# RaspberryPi.net
KiCad netlist of a schematic drawn in Altium Designer
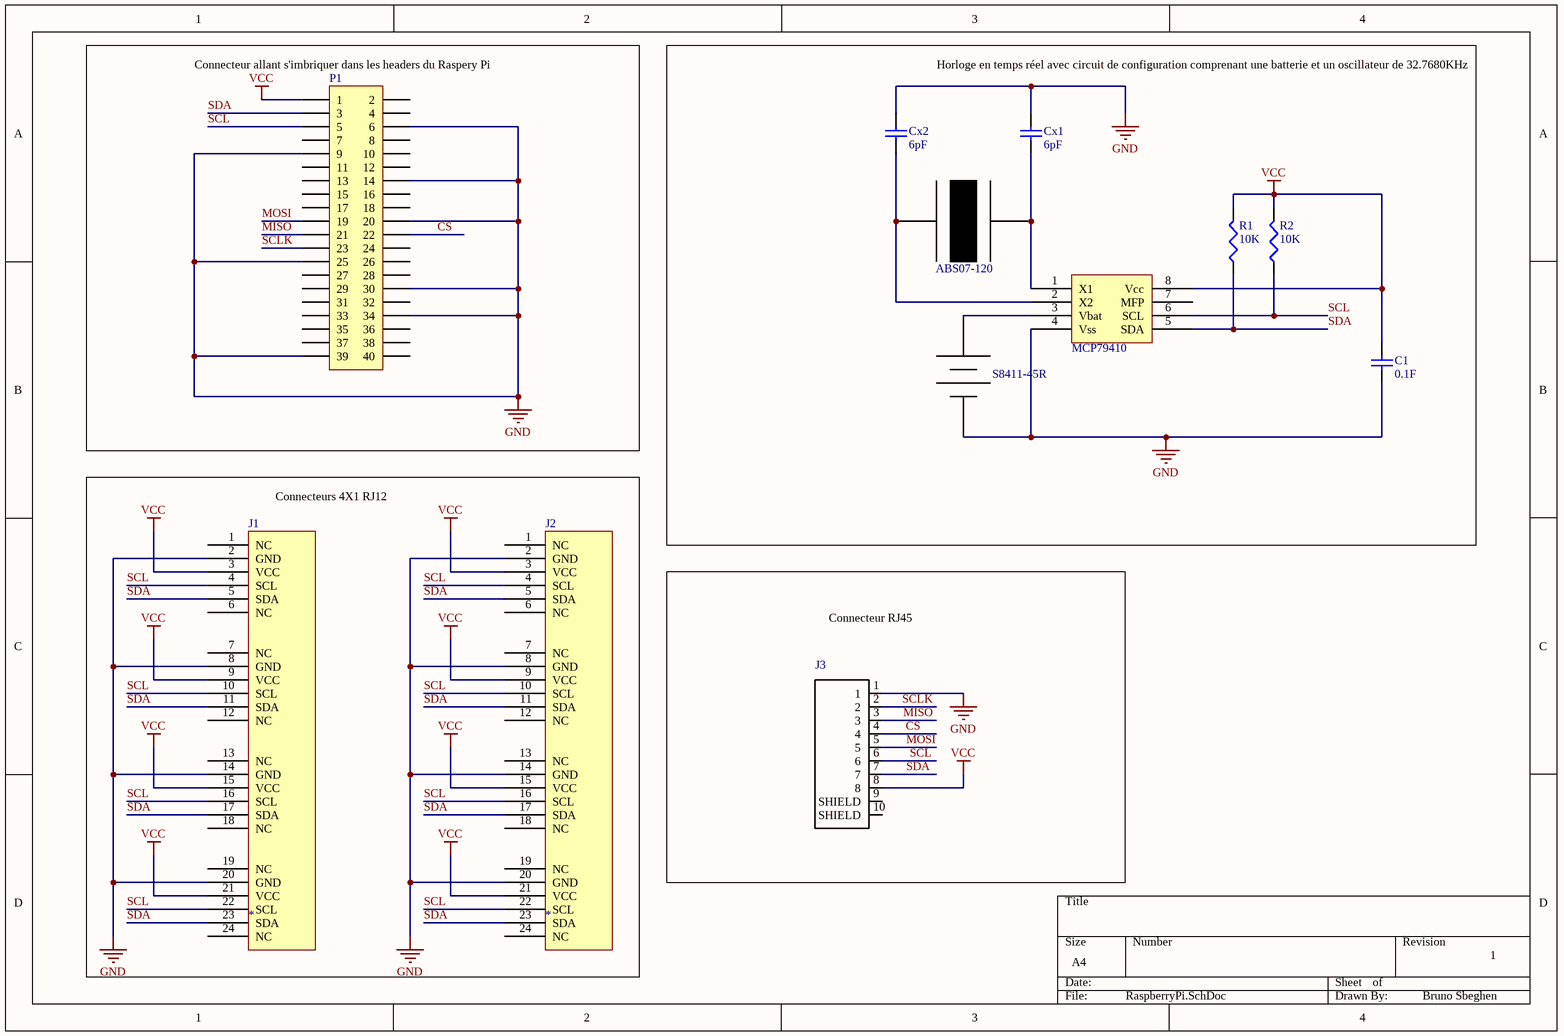
[diagram p0: RaspberryPi.SchDoc]

(export (version "E")
  (design (tool "Eeschema 10.0.6"))
  (components
    (comp (ref "ABS07-120")
      (value "*")
      (footprint "ECX-31B")
      (description "Oscillator 32.7680KHz")
      (libsource (lib "MOvIT-Detect PCB") (part "AB38T"))
    )
    (comp (ref "C1")
      (value "0.1F")
      (footprint "C0805")
      (description "Capacitor 0.1uF")
      (fields (field (name "Comment") "Cap 0.1uF") (field (name "PUBLISHER") "Altium Limited"))
      (libsource (lib "MOvIT-Detect PCB") (part "Cap 0.1uF"))
    )
    (comp (ref "Cx1")
      (value "6pF")
      (footprint "C0805")
      (description "Capacitor 6pF")
      (fields (field (name "Comment") "Cap 6pF") (field (name "PUBLISHER") "Altium Limited"))
      (libsource (lib "MOvIT-Detect PCB") (part "Cap 6pF"))
    )
    (comp (ref "Cx2")
      (value "6pF")
      (footprint "C0805")
      (description "Capacitor 6pF")
      (fields (field (name "Comment") "Cap 6pF") (field (name "PUBLISHER") "Altium Limited"))
      (libsource (lib "MOvIT-Detect PCB") (part "Cap 6pF"))
    )
    (comp (ref "J1")
      (value "*")
      (footprint "TM2RE-2424")
      (description "Connector MOD JACK 4pos")
      (libsource (lib "MOvIT-Detect PCB") (part "TM2RE-2424(50)"))
    )
    (comp (ref "J2")
      (value "*")
      (footprint "TM2RE-2424")
      (description "Connector MOD JACK 4pos")
      (libsource (lib "MOvIT-Detect PCB") (part "TM2RE-2424(50)"))
    )
    (comp (ref "J3")
      (value "RJ45-8N-B")
      (footprint "TE_RJ45-8N-B")
      (description "Corcom; Filter; Signal Line; Modular; 8 Contacts; 1 Port Through Hole")
      (fields (field (name "MF") "TE Connectivity"))
      (libsource (lib "MOvIT-Detect PCB") (part "RJ45-8N-B"))
    )
    (comp (ref "MCP79410")
      (value "*")
      (footprint "MCP79410")
      (description "RTC")
      (libsource (lib "MOvIT-Detect PCB") (part "MCP79410"))
    )
    (comp (ref "P1")
      (value "Header 20X2")
      (footprint "HDR2X20")
      (description "Header, 20-Pin, Dual row")
      (fields (field (name "PUBLISHER") "Altium Limited"))
      (libsource (lib "MOvIT-Detect PCB") (part "Header 20X2"))
    )
    (comp (ref "R1")
      (value "10K")
      (footprint "6-0805_N")
      (description "Resistor 10K")
      (fields (field (name "Comment") "Res 10K") (field (name "PUBLISHER") "Altium Limited"))
      (libsource (lib "MOvIT-Detect PCB") (part "Res 10K"))
    )
    (comp (ref "R2")
      (value "10K")
      (footprint "6-0805_N")
      (description "Resistor 10K")
      (fields (field (name "Comment") "Res 10K") (field (name "PUBLISHER") "Altium Limited"))
      (libsource (lib "MOvIT-Detect PCB") (part "Res 10K"))
    )
    (comp (ref "S8411-45R")
      (value "*")
      (footprint "S8411-45R")
      (description "12mm Battery holder")
      (libsource (lib "MOvIT-Detect PCB") (part "S8411-45R"))
    )
  )
  (nets
    (net (code "2") (name "/CS") (class "Default")
      (node (ref "J3") (pin "4") (pinfunction "4_4") (pintype "passive"))
      (node (ref "P1") (pin "22") (pinfunction "22_22") (pintype "passive"))
    )
    (net (code "3") (name "/MISO") (class "Default")
      (node (ref "J3") (pin "3") (pinfunction "3_3") (pintype "passive"))
      (node (ref "P1") (pin "21") (pinfunction "21_21") (pintype "passive"))
    )
    (net (code "4") (name "/MOSI") (class "Default")
      (node (ref "J3") (pin "5") (pinfunction "5_5") (pintype "passive"))
      (node (ref "P1") (pin "19") (pinfunction "19_19") (pintype "passive"))
    )
    (net (code "5") (name "/SCL") (class "Default")
      (node (ref "J1") (pin "10") (pinfunction "SCL_10") (pintype "passive"))
      (node (ref "J1") (pin "16") (pinfunction "SCL_16") (pintype "passive"))
      (node (ref "J1") (pin "22") (pinfunction "SCL_22") (pintype "passive"))
      (node (ref "J1") (pin "4") (pinfunction "SCL_4") (pintype "passive"))
      (node (ref "J2") (pin "10") (pinfunction "SCL_10") (pintype "passive"))
      (node (ref "J2") (pin "16") (pinfunction "SCL_16") (pintype "passive"))
      (node (ref "J2") (pin "22") (pinfunction "SCL_22") (pintype "passive"))
      (node (ref "J2") (pin "4") (pinfunction "SCL_4") (pintype "passive"))
      (node (ref "J3") (pin "6") (pinfunction "6_6") (pintype "passive"))
      (node (ref "MCP79410") (pin "6") (pinfunction "SCL_6") (pintype "passive"))
      (node (ref "P1") (pin "5") (pinfunction "5_5") (pintype "passive"))
      (node (ref "R2") (pin "1") (pinfunction "1_1") (pintype "passive"))
    )
    (net (code "6") (name "/SCLK") (class "Default")
      (node (ref "J3") (pin "2") (pinfunction "2_2") (pintype "passive"))
      (node (ref "P1") (pin "23") (pinfunction "23_23") (pintype "passive"))
    )
    (net (code "7") (name "/SDA") (class "Default")
      (node (ref "J1") (pin "11") (pinfunction "SDA_11") (pintype "passive"))
      (node (ref "J1") (pin "17") (pinfunction "SDA_17") (pintype "passive"))
      (node (ref "J1") (pin "23") (pinfunction "SDA_23") (pintype "passive"))
      (node (ref "J1") (pin "5") (pinfunction "SDA_5") (pintype "passive"))
      (node (ref "J2") (pin "11") (pinfunction "SDA_11") (pintype "passive"))
      (node (ref "J2") (pin "17") (pinfunction "SDA_17") (pintype "passive"))
      (node (ref "J2") (pin "23") (pinfunction "SDA_23") (pintype "passive"))
      (node (ref "J2") (pin "5") (pinfunction "SDA_5") (pintype "passive"))
      (node (ref "J3") (pin "7") (pinfunction "7_7") (pintype "passive"))
      (node (ref "MCP79410") (pin "5") (pinfunction "SDA_5") (pintype "passive"))
      (node (ref "P1") (pin "3") (pinfunction "3_3") (pintype "passive"))
      (node (ref "R1") (pin "1") (pinfunction "1_1") (pintype "passive"))
    )
    (net (code "8") (name "GND") (class "Default")
      (node (ref "C1") (pin "1") (pinfunction "1_1") (pintype "passive"))
      (node (ref "Cx1") (pin "2") (pinfunction "2_2") (pintype "passive"))
      (node (ref "Cx2") (pin "2") (pinfunction "2_2") (pintype "passive"))
      (node (ref "J1") (pin "14") (pinfunction "GND_14") (pintype "passive"))
      (node (ref "J1") (pin "2") (pinfunction "GND_2") (pintype "passive"))
      (node (ref "J1") (pin "20") (pinfunction "GND_20") (pintype "passive"))
      (node (ref "J1") (pin "8") (pinfunction "GND_8") (pintype "passive"))
      (node (ref "J2") (pin "14") (pinfunction "GND_14") (pintype "passive"))
      (node (ref "J2") (pin "2") (pinfunction "GND_2") (pintype "passive"))
      (node (ref "J2") (pin "20") (pinfunction "GND_20") (pintype "passive"))
      (node (ref "J2") (pin "8") (pinfunction "GND_8") (pintype "passive"))
      (node (ref "J3") (pin "1") (pinfunction "1_1") (pintype "passive"))
      (node (ref "MCP79410") (pin "4") (pinfunction "Vss_4") (pintype "passive"))
      (node (ref "P1") (pin "14") (pinfunction "14_14") (pintype "passive"))
      (node (ref "P1") (pin "20") (pinfunction "20_20") (pintype "passive"))
      (node (ref "P1") (pin "25") (pinfunction "25_25") (pintype "passive"))
      (node (ref "P1") (pin "30") (pinfunction "30_30") (pintype "passive"))
      (node (ref "P1") (pin "34") (pinfunction "34_34") (pintype "passive"))
      (node (ref "P1") (pin "39") (pinfunction "39_39") (pintype "passive"))
      (node (ref "P1") (pin "6") (pinfunction "6_6") (pintype "passive"))
      (node (ref "P1") (pin "9") (pinfunction "9_9") (pintype "passive"))
      (node (ref "S8411-45R") (pin "1") (pintype "passive"))
    )
    (net (code "9") (name "Net-(MCP79410-Vbat)") (class "Default")
      (node (ref "MCP79410") (pin "3") (pinfunction "Vbat_3") (pintype "passive"))
      (node (ref "S8411-45R") (pin "2") (pintype "passive"))
    )
    (net (code "10") (name "Net-(MCP79410-X1)") (class "Default")
      (node (ref "ABS07-120") (pin "2") (pintype "passive"))
      (node (ref "Cx1") (pin "1") (pinfunction "1_1") (pintype "passive"))
      (node (ref "MCP79410") (pin "1") (pinfunction "X1_1") (pintype "passive"))
    )
    (net (code "11") (name "Net-(MCP79410-X2)") (class "Default")
      (node (ref "ABS07-120") (pin "1") (pintype "passive"))
      (node (ref "Cx2") (pin "1") (pinfunction "1_1") (pintype "passive"))
      (node (ref "MCP79410") (pin "2") (pinfunction "X2_2") (pintype "passive"))
    )
    (net (code "12") (name "VCC") (class "Default")
      (node (ref "C1") (pin "2") (pinfunction "2_2") (pintype "passive"))
      (node (ref "J1") (pin "15") (pinfunction "VCC_15") (pintype "passive"))
      (node (ref "J1") (pin "21") (pinfunction "VCC_21") (pintype "passive"))
      (node (ref "J1") (pin "3") (pinfunction "VCC_3") (pintype "passive"))
      (node (ref "J1") (pin "9") (pinfunction "VCC_9") (pintype "passive"))
      (node (ref "J2") (pin "15") (pinfunction "VCC_15") (pintype "passive"))
      (node (ref "J2") (pin "21") (pinfunction "VCC_21") (pintype "passive"))
      (node (ref "J2") (pin "3") (pinfunction "VCC_3") (pintype "passive"))
      (node (ref "J2") (pin "9") (pinfunction "VCC_9") (pintype "passive"))
      (node (ref "J3") (pin "8") (pinfunction "8_8") (pintype "passive"))
      (node (ref "MCP79410") (pin "8") (pinfunction "Vcc_8") (pintype "passive"))
      (node (ref "P1") (pin "1") (pinfunction "1_1") (pintype "passive"))
      (node (ref "R1") (pin "2") (pinfunction "2_2") (pintype "passive"))
      (node (ref "R2") (pin "2") (pinfunction "2_2") (pintype "passive"))
    )
    (net (code "13") (name "unconnected-(J1-NC-Pad1)") (class "Default")
      (node (ref "J1") (pin "1") (pinfunction "NC_1") (pintype "passive"))
    )
    (net (code "14") (name "unconnected-(J1-NC-Pad6)") (class "Default")
      (node (ref "J1") (pin "6") (pinfunction "NC_6") (pintype "passive"))
    )
    (net (code "15") (name "unconnected-(J1-NC-Pad7)") (class "Default")
      (node (ref "J1") (pin "7") (pinfunction "NC_7") (pintype "passive"))
    )
    (net (code "16") (name "unconnected-(J1-NC-Pad12)") (class "Default")
      (node (ref "J1") (pin "12") (pinfunction "NC_12") (pintype "passive"))
    )
    (net (code "17") (name "unconnected-(J1-NC-Pad13)") (class "Default")
      (node (ref "J1") (pin "13") (pinfunction "NC_13") (pintype "passive"))
    )
    (net (code "18") (name "unconnected-(J1-NC-Pad18)") (class "Default")
      (node (ref "J1") (pin "18") (pinfunction "NC_18") (pintype "passive"))
    )
    (net (code "19") (name "unconnected-(J1-NC-Pad19)") (class "Default")
      (node (ref "J1") (pin "19") (pinfunction "NC_19") (pintype "passive"))
    )
    (net (code "20") (name "unconnected-(J1-NC-Pad24)") (class "Default")
      (node (ref "J1") (pin "24") (pinfunction "NC_24") (pintype "passive"))
    )
    (net (code "21") (name "unconnected-(J2-NC-Pad1)") (class "Default")
      (node (ref "J2") (pin "1") (pinfunction "NC_1") (pintype "passive"))
    )
    (net (code "22") (name "unconnected-(J2-NC-Pad6)") (class "Default")
      (node (ref "J2") (pin "6") (pinfunction "NC_6") (pintype "passive"))
    )
    (net (code "23") (name "unconnected-(J2-NC-Pad7)") (class "Default")
      (node (ref "J2") (pin "7") (pinfunction "NC_7") (pintype "passive"))
    )
    (net (code "24") (name "unconnected-(J2-NC-Pad12)") (class "Default")
      (node (ref "J2") (pin "12") (pinfunction "NC_12") (pintype "passive"))
    )
    (net (code "25") (name "unconnected-(J2-NC-Pad13)") (class "Default")
      (node (ref "J2") (pin "13") (pinfunction "NC_13") (pintype "passive"))
    )
    (net (code "26") (name "unconnected-(J2-NC-Pad18)") (class "Default")
      (node (ref "J2") (pin "18") (pinfunction "NC_18") (pintype "passive"))
    )
    (net (code "27") (name "unconnected-(J2-NC-Pad19)") (class "Default")
      (node (ref "J2") (pin "19") (pinfunction "NC_19") (pintype "passive"))
    )
    (net (code "28") (name "unconnected-(J2-NC-Pad24)") (class "Default")
      (node (ref "J2") (pin "24") (pinfunction "NC_24") (pintype "passive"))
    )
    (net (code "29") (name "unconnected-(J3-SHIELD-Pad9)") (class "Default")
      (node (ref "J3") (pin "9") (pinfunction "SHIELD_9") (pintype "passive"))
    )
    (net (code "30") (name "unconnected-(J3-SHIELD-Pad10)") (class "Default")
      (node (ref "J3") (pin "10") (pinfunction "SHIELD_10") (pintype "passive"))
    )
    (net (code "31") (name "unconnected-(MCP79410-MFP-Pad7)") (class "Default")
      (node (ref "MCP79410") (pin "7") (pinfunction "MFP_7") (pintype "passive"))
    )
    (net (code "32") (name "unconnected-(P1-Pad2)") (class "Default")
      (node (ref "P1") (pin "2") (pinfunction "2_2") (pintype "passive"))
    )
    (net (code "33") (name "unconnected-(P1-Pad4)") (class "Default")
      (node (ref "P1") (pin "4") (pinfunction "4_4") (pintype "passive"))
    )
    (net (code "34") (name "unconnected-(P1-Pad7)") (class "Default")
      (node (ref "P1") (pin "7") (pinfunction "7_7") (pintype "passive"))
    )
    (net (code "35") (name "unconnected-(P1-Pad8)") (class "Default")
      (node (ref "P1") (pin "8") (pinfunction "8_8") (pintype "passive"))
    )
    (net (code "36") (name "unconnected-(P1-Pad10)") (class "Default")
      (node (ref "P1") (pin "10") (pinfunction "10_10") (pintype "passive"))
    )
    (net (code "37") (name "unconnected-(P1-Pad11)") (class "Default")
      (node (ref "P1") (pin "11") (pinfunction "11_11") (pintype "passive"))
    )
    (net (code "38") (name "unconnected-(P1-Pad12)") (class "Default")
      (node (ref "P1") (pin "12") (pinfunction "12_12") (pintype "passive"))
    )
    (net (code "39") (name "unconnected-(P1-Pad13)") (class "Default")
      (node (ref "P1") (pin "13") (pinfunction "13_13") (pintype "passive"))
    )
    (net (code "40") (name "unconnected-(P1-Pad15)") (class "Default")
      (node (ref "P1") (pin "15") (pinfunction "15_15") (pintype "passive"))
    )
    (net (code "41") (name "unconnected-(P1-Pad16)") (class "Default")
      (node (ref "P1") (pin "16") (pinfunction "16_16") (pintype "passive"))
    )
    (net (code "42") (name "unconnected-(P1-Pad17)") (class "Default")
      (node (ref "P1") (pin "17") (pinfunction "17_17") (pintype "passive"))
    )
    (net (code "43") (name "unconnected-(P1-Pad18)") (class "Default")
      (node (ref "P1") (pin "18") (pinfunction "18_18") (pintype "passive"))
    )
    (net (code "44") (name "unconnected-(P1-Pad24)") (class "Default")
      (node (ref "P1") (pin "24") (pinfunction "24_24") (pintype "passive"))
    )
    (net (code "45") (name "unconnected-(P1-Pad26)") (class "Default")
      (node (ref "P1") (pin "26") (pinfunction "26_26") (pintype "passive"))
    )
    (net (code "46") (name "unconnected-(P1-Pad27)") (class "Default")
      (node (ref "P1") (pin "27") (pinfunction "27_27") (pintype "passive"))
    )
    (net (code "47") (name "unconnected-(P1-Pad28)") (class "Default")
      (node (ref "P1") (pin "28") (pinfunction "28_28") (pintype "passive"))
    )
    (net (code "48") (name "unconnected-(P1-Pad29)") (class "Default")
      (node (ref "P1") (pin "29") (pinfunction "29_29") (pintype "passive"))
    )
    (net (code "49") (name "unconnected-(P1-Pad31)") (class "Default")
      (node (ref "P1") (pin "31") (pinfunction "31_31") (pintype "passive"))
    )
    (net (code "50") (name "unconnected-(P1-Pad32)") (class "Default")
      (node (ref "P1") (pin "32") (pinfunction "32_32") (pintype "passive"))
    )
    (net (code "51") (name "unconnected-(P1-Pad33)") (class "Default")
      (node (ref "P1") (pin "33") (pinfunction "33_33") (pintype "passive"))
    )
    (net (code "52") (name "unconnected-(P1-Pad35)") (class "Default")
      (node (ref "P1") (pin "35") (pinfunction "35_35") (pintype "passive"))
    )
    (net (code "53") (name "unconnected-(P1-Pad36)") (class "Default")
      (node (ref "P1") (pin "36") (pinfunction "36_36") (pintype "passive"))
    )
    (net (code "54") (name "unconnected-(P1-Pad37)") (class "Default")
      (node (ref "P1") (pin "37") (pinfunction "37_37") (pintype "passive"))
    )
    (net (code "55") (name "unconnected-(P1-Pad38)") (class "Default")
      (node (ref "P1") (pin "38") (pinfunction "38_38") (pintype "passive"))
    )
    (net (code "56") (name "unconnected-(P1-Pad40)") (class "Default")
      (node (ref "P1") (pin "40") (pinfunction "40_40") (pintype "passive"))
    )
  )
)
